# RemoteLora.net
KiCad netlist of a schematic drawn in Altium Designer
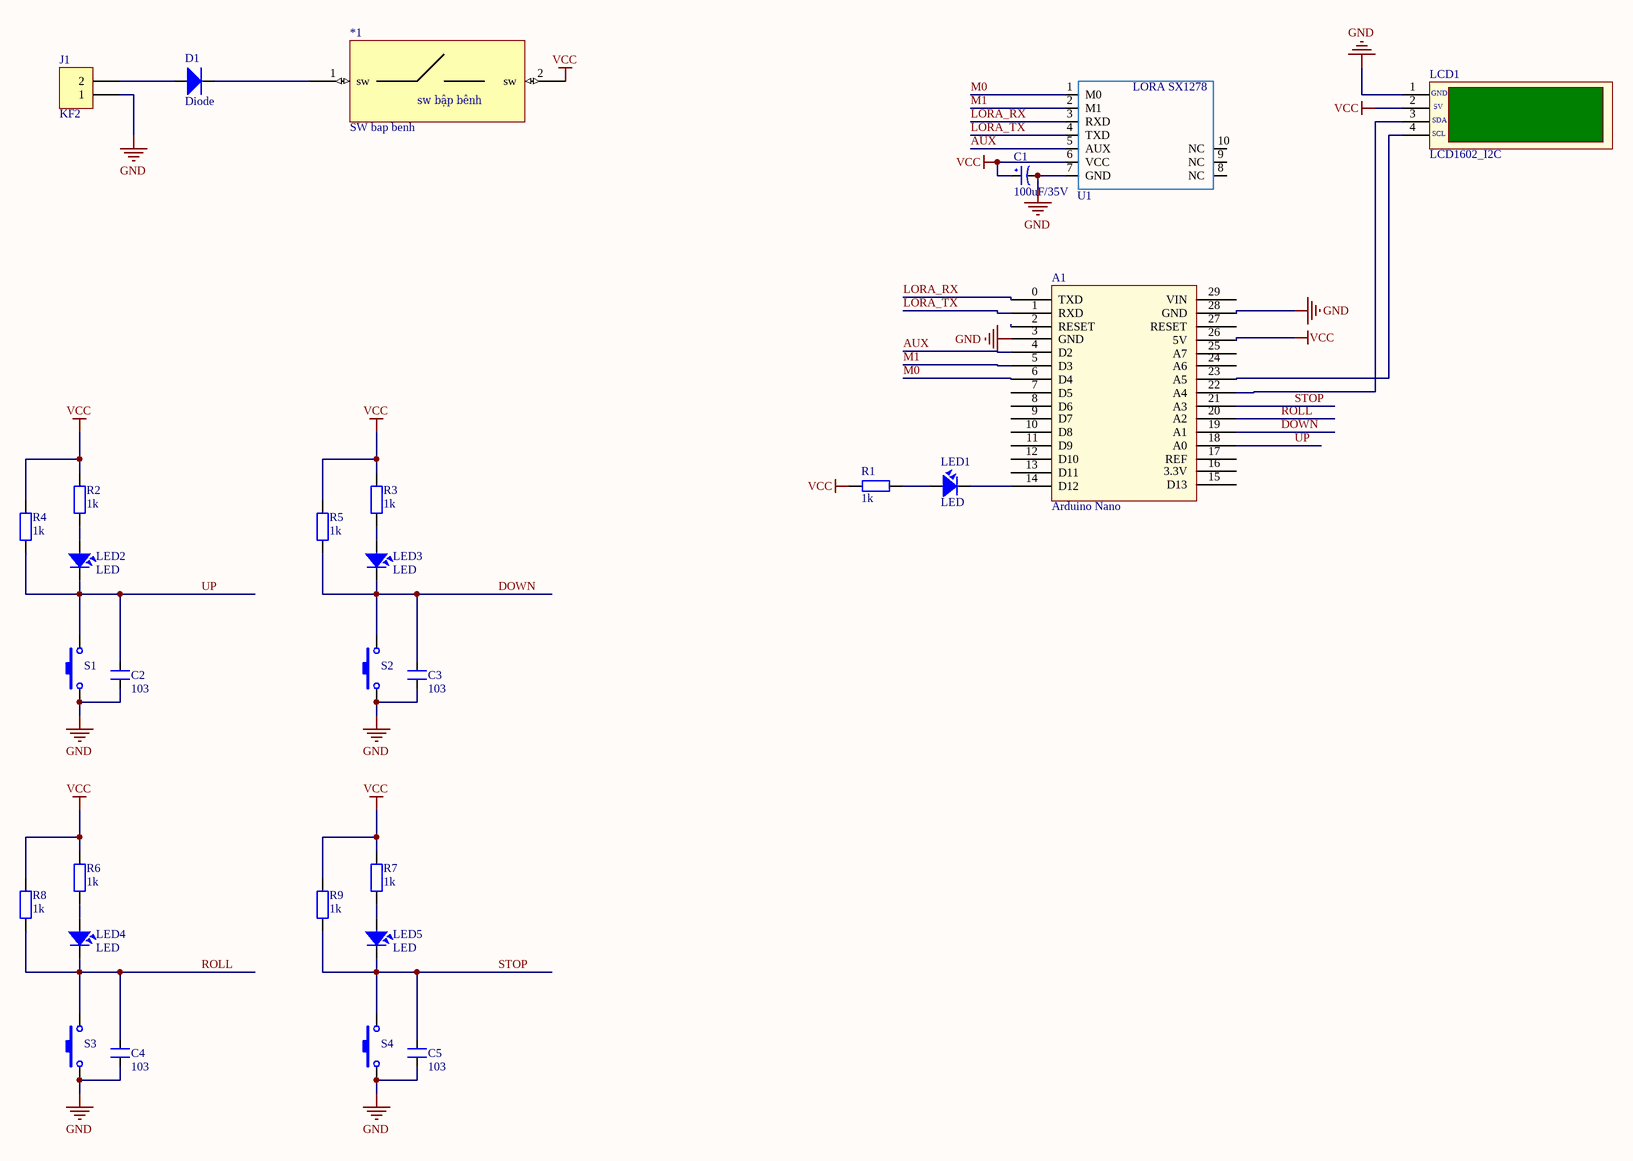
[diagram p0: RemoteLora.SchDoc]

(export (version "E")
  (design (tool "Eeschema 10.0.6"))
  (components
    (comp (ref "*1")
      (value "SW bap benh")
      (footprint "SW bapbenh")
      (libsource (lib "Tesla_Thinh") (part "SW bap benh"))
    )
    (comp (ref "A1")
      (value "Arduino Nano")
      (footprint "Arduino Nano")
      (libsource (lib "OBIT_TESLA") (part "Arduino Nano"))
    )
    (comp (ref "C1")
      (value "100uF/35V")
      (footprint "CP1.5/3.4")
      (description "Cap 100uF/35V - 470uF/16V")
      (libsource (lib "OBIT_TESLA") (part "CP3"))
    )
    (comp (ref "C2")
      (value "103")
      (footprint "SM-0805")
      (description "Cap SMD")
      (libsource (lib "OBIT_TESLA") (part "CM"))
    )
    (comp (ref "C3")
      (value "103")
      (footprint "SM-0805")
      (description "Cap SMD")
      (libsource (lib "OBIT_TESLA") (part "CM"))
    )
    (comp (ref "C4")
      (value "103")
      (footprint "SM-0805")
      (description "Cap SMD")
      (libsource (lib "OBIT_TESLA") (part "CM"))
    )
    (comp (ref "C5")
      (value "103")
      (footprint "SM-0805")
      (description "Cap SMD")
      (libsource (lib "OBIT_TESLA") (part "CM"))
    )
    (comp (ref "D1") (value "Diode") (footprint "D0.5A") (libsource (lib "OBIT_TESLA") (part "Diode")))
    (comp (ref "J1")
      (value "KF2")
      (footprint "KF2-3.5")
      (fields
        (field (name "MANUFACTURER") "Würth Elektronik eiSos GmbH")
        (field (name "PARTNO") "691103110002")
        (field (name "CREATED BY") "Karrer Zheng")
      )
      (libsource (lib "OBIT_TESLA") (part "KF2"))
    )
    (comp (ref "LCD1")
      (value "LCD1602_I2C")
      (footprint "LCD1602_I2C")
      (libsource (lib "OBIT_TESLA") (part "LCD1602_I2C"))
    )
    (comp (ref "LED1") (value "LED") (footprint "LED-5-BLUE") (libsource (lib "OBIT_TESLA") (part "LED")))
    (comp (ref "LED2") (value "LED") (footprint "LED-5-BLUE") (libsource (lib "OBIT_TESLA") (part "LED")))
    (comp (ref "LED3") (value "LED") (footprint "LED-5-BLUE") (libsource (lib "OBIT_TESLA") (part "LED")))
    (comp (ref "LED4") (value "LED") (footprint "LED-5-BLUE") (libsource (lib "OBIT_TESLA") (part "LED")))
    (comp (ref "LED5") (value "LED") (footprint "LED-5-BLUE") (libsource (lib "OBIT_TESLA") (part "LED")))
    (comp (ref "R1")
      (value "1k")
      (footprint "RES-1/4W")
      (description "Resistor R1/4W")
      (libsource (lib "OBIT_TESLA") (part "R"))
    )
    (comp (ref "R2")
      (value "1k")
      (footprint "RES-1/4W")
      (description "Resistor R1/4W")
      (libsource (lib "OBIT_TESLA") (part "R"))
    )
    (comp (ref "R3")
      (value "1k")
      (footprint "RES-1/4W")
      (description "Resistor R1/4W")
      (libsource (lib "OBIT_TESLA") (part "R"))
    )
    (comp (ref "R4")
      (value "1k")
      (footprint "RES-1/4W")
      (description "Resistor R1/4W")
      (libsource (lib "OBIT_TESLA") (part "R"))
    )
    (comp (ref "R5")
      (value "1k")
      (footprint "RES-1/4W")
      (description "Resistor R1/4W")
      (libsource (lib "OBIT_TESLA") (part "R"))
    )
    (comp (ref "R6")
      (value "1k")
      (footprint "RES-1/4W")
      (description "Resistor R1/4W")
      (libsource (lib "OBIT_TESLA") (part "R"))
    )
    (comp (ref "R7")
      (value "1k")
      (footprint "RES-1/4W")
      (description "Resistor R1/4W")
      (libsource (lib "OBIT_TESLA") (part "R"))
    )
    (comp (ref "R8")
      (value "1k")
      (footprint "RES-1/4W")
      (description "Resistor R1/4W")
      (libsource (lib "OBIT_TESLA") (part "R"))
    )
    (comp (ref "R9")
      (value "1k")
      (footprint "RES-1/4W")
      (description "Resistor R1/4W")
      (libsource (lib "OBIT_TESLA") (part "R"))
    )
    (comp (ref "S1")
      (value "SW")
      (footprint "BUTTON  ROUND")
      (description "Switch-Button")
      (fields (field (name "PUBLISHER") "Altium Limited"))
      (libsource (lib "OBIT_TESLA") (part "SW-Button"))
    )
    (comp (ref "S2")
      (value "SW")
      (footprint "BUTTON  ROUND")
      (description "Switch-Button")
      (fields (field (name "PUBLISHER") "Altium Limited"))
      (libsource (lib "OBIT_TESLA") (part "SW-Button"))
    )
    (comp (ref "S3")
      (value "SW")
      (footprint "BUTTON  ROUND")
      (description "Switch-Button")
      (fields (field (name "PUBLISHER") "Altium Limited"))
      (libsource (lib "OBIT_TESLA") (part "SW-Button"))
    )
    (comp (ref "S4")
      (value "SW")
      (footprint "BUTTON  ROUND")
      (description "Switch-Button")
      (fields (field (name "PUBLISHER") "Altium Limited"))
      (libsource (lib "OBIT_TESLA") (part "SW-Button"))
    )
    (comp (ref "U1")
      (value "Lora SX1278 UART")
      (footprint "Lora_uart_sx1278")
      (libsource (lib "OBIT_TESLA") (part "Lora SX1278 UART"))
    )
  )
  (nets
    (net (code "1") (name "/AUX") (class "Default")
      (node (ref "A1") (pin "4") (pinfunction "D2_4") (pintype "passive"))
      (node (ref "U1") (pin "5") (pinfunction "AUX_5") (pintype "passive"))
    )
    (net (code "2") (name "/DOWN") (class "Default")
      (node (ref "A1") (pin "19") (pinfunction "A1_19") (pintype "passive"))
      (node (ref "C3") (pin "2") (pinfunction "2_2") (pintype "passive"))
      (node (ref "LED3") (pin "2") (pinfunction "2_2") (pintype "passive"))
      (node (ref "R5") (pin "1") (pinfunction "1_1") (pintype "passive"))
      (node (ref "S2") (pin "2") (pinfunction "2_2") (pintype "passive"))
    )
    (net (code "3") (name "/LORA_RX") (class "Default")
      (node (ref "A1") (pin "0") (pinfunction "TXD_0") (pintype "passive"))
      (node (ref "U1") (pin "3") (pinfunction "RXD_3") (pintype "passive"))
    )
    (net (code "4") (name "/LORA_TX") (class "Default")
      (node (ref "A1") (pin "1") (pinfunction "RXD_1") (pintype "passive"))
      (node (ref "U1") (pin "4") (pinfunction "TXD_4") (pintype "passive"))
    )
    (net (code "5") (name "/M0") (class "Default")
      (node (ref "A1") (pin "6") (pinfunction "D4_6") (pintype "passive"))
      (node (ref "U1") (pin "1") (pinfunction "M0_1") (pintype "passive"))
    )
    (net (code "6") (name "/M1") (class "Default")
      (node (ref "A1") (pin "5") (pinfunction "D3_5") (pintype "passive"))
      (node (ref "U1") (pin "2") (pinfunction "M1_2") (pintype "passive"))
    )
    (net (code "7") (name "/ROLL") (class "Default")
      (node (ref "A1") (pin "20") (pinfunction "A2_20") (pintype "passive"))
      (node (ref "C4") (pin "2") (pinfunction "2_2") (pintype "passive"))
      (node (ref "LED4") (pin "2") (pinfunction "2_2") (pintype "passive"))
      (node (ref "R8") (pin "1") (pinfunction "1_1") (pintype "passive"))
      (node (ref "S3") (pin "2") (pinfunction "2_2") (pintype "passive"))
    )
    (net (code "8") (name "/STOP") (class "Default")
      (node (ref "A1") (pin "21") (pinfunction "A3_21") (pintype "passive"))
      (node (ref "C5") (pin "2") (pinfunction "2_2") (pintype "passive"))
      (node (ref "LED5") (pin "2") (pinfunction "2_2") (pintype "passive"))
      (node (ref "R9") (pin "1") (pinfunction "1_1") (pintype "passive"))
      (node (ref "S4") (pin "2") (pinfunction "2_2") (pintype "passive"))
    )
    (net (code "9") (name "/UP") (class "Default")
      (node (ref "A1") (pin "18") (pinfunction "A0_18") (pintype "passive"))
      (node (ref "C2") (pin "2") (pinfunction "2_2") (pintype "passive"))
      (node (ref "LED2") (pin "2") (pinfunction "2_2") (pintype "passive"))
      (node (ref "R4") (pin "1") (pinfunction "1_1") (pintype "passive"))
      (node (ref "S1") (pin "2") (pinfunction "2_2") (pintype "passive"))
    )
    (net (code "10") (name "GND") (class "Default")
      (node (ref "A1") (pin "28") (pinfunction "GND_28") (pintype "passive"))
      (node (ref "A1") (pin "3") (pinfunction "GND_3") (pintype "passive"))
      (node (ref "C1") (pin "2") (pinfunction "2_2") (pintype "passive"))
      (node (ref "C2") (pin "1") (pinfunction "1_1") (pintype "passive"))
      (node (ref "C3") (pin "1") (pinfunction "1_1") (pintype "passive"))
      (node (ref "C4") (pin "1") (pinfunction "1_1") (pintype "passive"))
      (node (ref "C5") (pin "1") (pinfunction "1_1") (pintype "passive"))
      (node (ref "J1") (pin "1") (pinfunction "1_1") (pintype "passive"))
      (node (ref "LCD1") (pin "1") (pinfunction "GND_1") (pintype "passive"))
      (node (ref "S1") (pin "1") (pinfunction "1_1") (pintype "passive"))
      (node (ref "S2") (pin "1") (pinfunction "1_1") (pintype "passive"))
      (node (ref "S3") (pin "1") (pinfunction "1_1") (pintype "passive"))
      (node (ref "S4") (pin "1") (pinfunction "1_1") (pintype "passive"))
      (node (ref "U1") (pin "7") (pinfunction "GND_7") (pintype "passive"))
    )
    (net (code "11") (name "Net-(*1-sw-Pad1)") (class "Default")
      (node (ref "*1") (pin "1") (pinfunction "sw_1") (pintype "bidirectional"))
      (node (ref "D1") (pin "2") (pinfunction "2_2") (pintype "passive"))
    )
    (net (code "12") (name "Net-(A1-A4)") (class "Default")
      (node (ref "A1") (pin "22") (pinfunction "A4_22") (pintype "passive"))
      (node (ref "LCD1") (pin "3") (pinfunction "SDA_3") (pintype "passive"))
    )
    (net (code "13") (name "Net-(A1-A5)") (class "Default")
      (node (ref "A1") (pin "23") (pinfunction "A5_23") (pintype "passive"))
      (node (ref "LCD1") (pin "4") (pinfunction "SCL_4") (pintype "passive"))
    )
    (net (code "14") (name "Net-(A1-D12)") (class "Default")
      (node (ref "A1") (pin "14") (pinfunction "D12_14") (pintype "passive"))
      (node (ref "LED1") (pin "2") (pinfunction "2_2") (pintype "passive"))
    )
    (net (code "15") (name "Net-(D1-Pad1)") (class "Default")
      (node (ref "D1") (pin "1") (pinfunction "1_1") (pintype "passive"))
      (node (ref "J1") (pin "2") (pinfunction "2_2") (pintype "passive"))
    )
    (net (code "16") (name "Net-(LED1-Pad1)") (class "Default")
      (node (ref "LED1") (pin "1") (pinfunction "1_1") (pintype "passive"))
      (node (ref "R1") (pin "2") (pinfunction "2_2") (pintype "passive"))
    )
    (net (code "17") (name "Net-(LED2-Pad1)") (class "Default")
      (node (ref "LED2") (pin "1") (pinfunction "1_1") (pintype "passive"))
      (node (ref "R2") (pin "1") (pinfunction "1_1") (pintype "passive"))
    )
    (net (code "18") (name "Net-(LED3-Pad1)") (class "Default")
      (node (ref "LED3") (pin "1") (pinfunction "1_1") (pintype "passive"))
      (node (ref "R3") (pin "1") (pinfunction "1_1") (pintype "passive"))
    )
    (net (code "19") (name "Net-(LED4-Pad1)") (class "Default")
      (node (ref "LED4") (pin "1") (pinfunction "1_1") (pintype "passive"))
      (node (ref "R6") (pin "1") (pinfunction "1_1") (pintype "passive"))
    )
    (net (code "20") (name "Net-(LED5-Pad1)") (class "Default")
      (node (ref "LED5") (pin "1") (pinfunction "1_1") (pintype "passive"))
      (node (ref "R7") (pin "1") (pinfunction "1_1") (pintype "passive"))
    )
    (net (code "21") (name "VCC") (class "Default")
      (node (ref "*1") (pin "2") (pinfunction "sw_2") (pintype "bidirectional"))
      (node (ref "A1") (pin "26") (pinfunction "5V_26") (pintype "passive"))
      (node (ref "C1") (pin "1") (pinfunction "1_1") (pintype "passive"))
      (node (ref "LCD1") (pin "2") (pinfunction "VCC_2") (pintype "passive"))
      (node (ref "R1") (pin "1") (pinfunction "1_1") (pintype "passive"))
      (node (ref "R2") (pin "2") (pinfunction "2_2") (pintype "passive"))
      (node (ref "R3") (pin "2") (pinfunction "2_2") (pintype "passive"))
      (node (ref "R4") (pin "2") (pinfunction "2_2") (pintype "passive"))
      (node (ref "R5") (pin "2") (pinfunction "2_2") (pintype "passive"))
      (node (ref "R6") (pin "2") (pinfunction "2_2") (pintype "passive"))
      (node (ref "R7") (pin "2") (pinfunction "2_2") (pintype "passive"))
      (node (ref "R8") (pin "2") (pinfunction "2_2") (pintype "passive"))
      (node (ref "R9") (pin "2") (pinfunction "2_2") (pintype "passive"))
      (node (ref "U1") (pin "6") (pinfunction "VCC_6") (pintype "passive"))
    )
    (net (code "22") (name "unconnected-(A1-3.3V-Pad16)") (class "Default")
      (node (ref "A1") (pin "16") (pinfunction "3.3V_16") (pintype "passive"))
    )
    (net (code "23") (name "unconnected-(A1-A6-Pad24)") (class "Default")
      (node (ref "A1") (pin "24") (pinfunction "A6_24") (pintype "passive"))
    )
    (net (code "24") (name "unconnected-(A1-A7-Pad25)") (class "Default")
      (node (ref "A1") (pin "25") (pinfunction "A7_25") (pintype "passive"))
    )
    (net (code "25") (name "unconnected-(A1-D5-Pad7)") (class "Default")
      (node (ref "A1") (pin "7") (pinfunction "D5_7") (pintype "passive"))
    )
    (net (code "26") (name "unconnected-(A1-D6-Pad8)") (class "Default")
      (node (ref "A1") (pin "8") (pinfunction "D6_8") (pintype "passive"))
    )
    (net (code "27") (name "unconnected-(A1-D7-Pad9)") (class "Default")
      (node (ref "A1") (pin "9") (pinfunction "D7_9") (pintype "passive"))
    )
    (net (code "28") (name "unconnected-(A1-D8-Pad10)") (class "Default")
      (node (ref "A1") (pin "10") (pinfunction "D8_10") (pintype "passive"))
    )
    (net (code "29") (name "unconnected-(A1-D9-Pad11)") (class "Default")
      (node (ref "A1") (pin "11") (pinfunction "D9_11") (pintype "passive"))
    )
    (net (code "30") (name "unconnected-(A1-D10-Pad12)") (class "Default")
      (node (ref "A1") (pin "12") (pinfunction "D10_12") (pintype "passive"))
    )
    (net (code "31") (name "unconnected-(A1-D11-Pad13)") (class "Default")
      (node (ref "A1") (pin "13") (pinfunction "D11_13") (pintype "passive"))
    )
    (net (code "32") (name "unconnected-(A1-D13-Pad15)") (class "Default")
      (node (ref "A1") (pin "15") (pinfunction "D13_15") (pintype "passive"))
    )
    (net (code "33") (name "unconnected-(A1-REF-Pad17)") (class "Default")
      (node (ref "A1") (pin "17") (pinfunction "REF_17") (pintype "passive"))
    )
    (net (code "34") (name "unconnected-(A1-RESET-Pad2)") (class "Default")
      (node (ref "A1") (pin "2") (pinfunction "RESET_2") (pintype "passive"))
    )
    (net (code "35") (name "unconnected-(A1-RESET-Pad27)") (class "Default")
      (node (ref "A1") (pin "27") (pinfunction "RESET_27") (pintype "passive"))
    )
    (net (code "36") (name "unconnected-(A1-VIN-Pad29)") (class "Default")
      (node (ref "A1") (pin "29") (pinfunction "VIN_29") (pintype "passive"))
    )
    (net (code "37") (name "unconnected-(U1-NC-Pad8)") (class "Default")
      (node (ref "U1") (pin "8") (pinfunction "NC_8") (pintype "passive"))
    )
    (net (code "38") (name "unconnected-(U1-NC-Pad9)") (class "Default")
      (node (ref "U1") (pin "9") (pinfunction "NC_9") (pintype "passive"))
    )
    (net (code "39") (name "unconnected-(U1-NC-Pad10)") (class "Default")
      (node (ref "U1") (pin "10") (pinfunction "NC_10") (pintype "passive"))
    )
  )
)
